# ProgrammerBoardV1_1.net
KiCad netlist of a schematic drawn in EAGLE
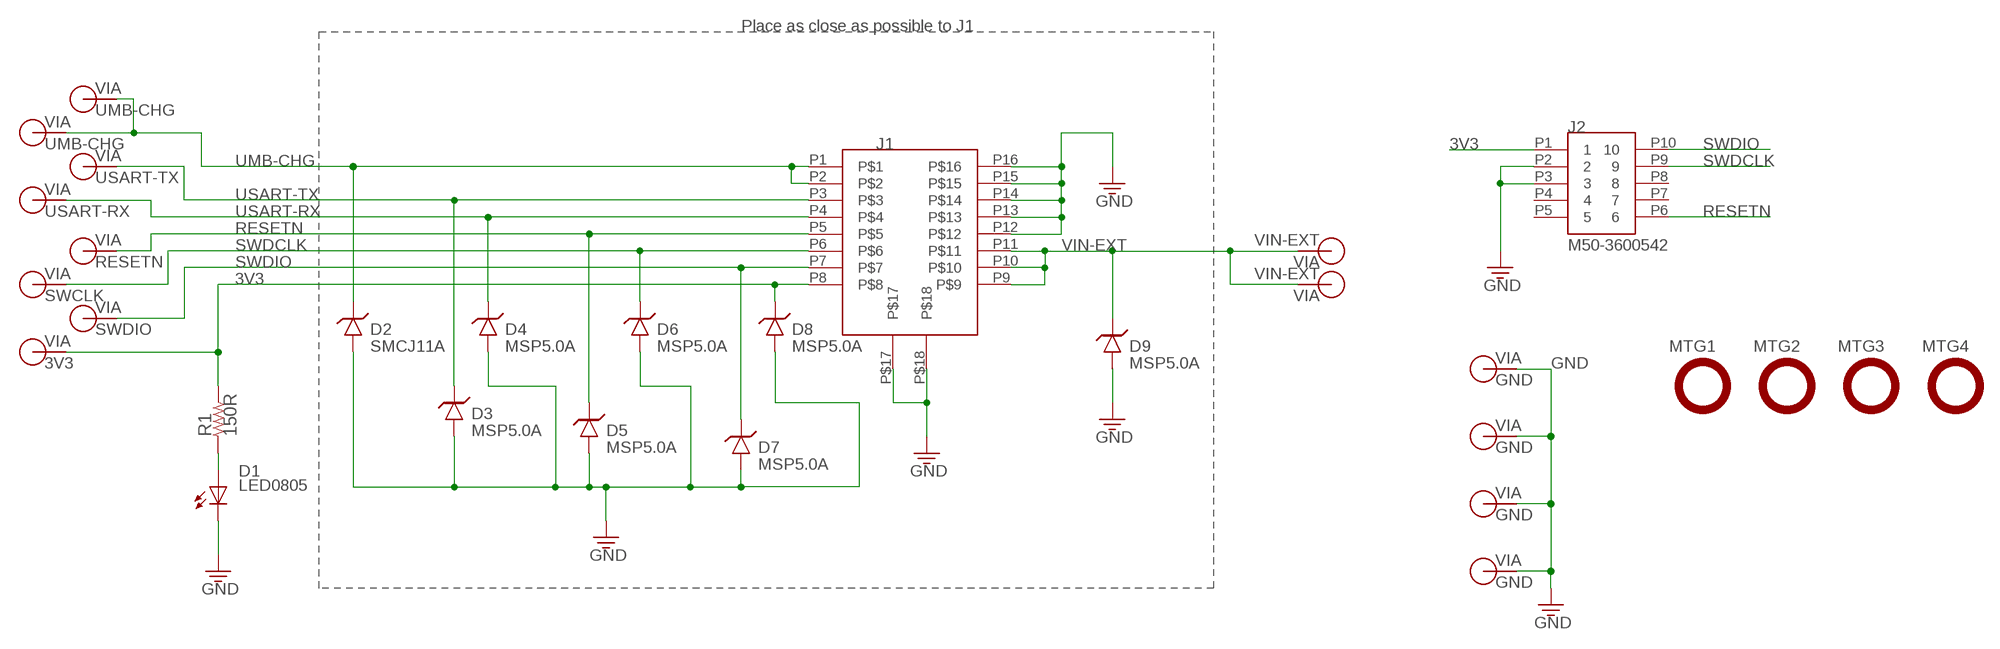
[diagram p0: schematic, sheet 1]

(export (version "E")
  (design (tool "Eeschema 10.0.6"))
  (components
    (comp (ref "D1")
      (value "LED0805")
      (footprint "eagle-import:0805-D")
      (libsource (lib "eagle-import") (part "LED0805"))
    )
    (comp (ref "D2")
      (value "SMCJ11A")
      (footprint "eagle-import:DO-214AB")
      (libsource (lib "eagle-import") (part "TVSSMCJ11A"))
    )
    (comp (ref "D3")
      (value "MSP5.0A")
      (footprint "eagle-import:MICROSMP")
      (libsource (lib "eagle-import") (part "TVSMSP"))
    )
    (comp (ref "D4")
      (value "MSP5.0A")
      (footprint "eagle-import:MICROSMP")
      (libsource (lib "eagle-import") (part "TVSMSP"))
    )
    (comp (ref "D5")
      (value "MSP5.0A")
      (footprint "eagle-import:MICROSMP")
      (libsource (lib "eagle-import") (part "TVSMSP"))
    )
    (comp (ref "D6")
      (value "MSP5.0A")
      (footprint "eagle-import:MICROSMP")
      (libsource (lib "eagle-import") (part "TVSMSP"))
    )
    (comp (ref "D7")
      (value "MSP5.0A")
      (footprint "eagle-import:MICROSMP")
      (libsource (lib "eagle-import") (part "TVSMSP"))
    )
    (comp (ref "D8")
      (value "MSP5.0A")
      (footprint "eagle-import:MICROSMP")
      (libsource (lib "eagle-import") (part "TVSMSP"))
    )
    (comp (ref "D9")
      (value "MSP5.0A")
      (footprint "eagle-import:MICROSMP")
      (libsource (lib "eagle-import") (part "TVSMSP"))
    )
    (comp (ref "J1")
      (value "FFC-16REVERSE")
      (footprint "eagle-import:68611614422-REVERSE")
      (libsource (lib "eagle-import") (part "FFC-16REVERSE"))
    )
    (comp (ref "J2")
      (value "M50-3600542")
      (footprint "eagle-import:10PINMALE")
      (libsource (lib "eagle-import") (part "10PINMALE"))
    )
    (comp (ref "MTG1")
      (value "MTG-NPTH-M2")
      (footprint "eagle-import:M2-NPTH")
      (libsource (lib "eagle-import") (part "MTG-NPTH-M2"))
    )
    (comp (ref "MTG2")
      (value "MTG-NPTH-M2")
      (footprint "eagle-import:M2-NPTH")
      (libsource (lib "eagle-import") (part "MTG-NPTH-M2"))
    )
    (comp (ref "MTG3")
      (value "MTG-NPTH-M2")
      (footprint "eagle-import:M2-NPTH")
      (libsource (lib "eagle-import") (part "MTG-NPTH-M2"))
    )
    (comp (ref "MTG4")
      (value "MTG-NPTH-M2")
      (footprint "eagle-import:M2-NPTH")
      (libsource (lib "eagle-import") (part "MTG-NPTH-M2"))
    )
    (comp (ref "R1")
      (value "150R")
      (footprint "eagle-import:0805")
      (libsource (lib "eagle-import") (part "RES0805"))
    )
    (comp (ref "V1")
      (value "GND")
      (footprint "eagle-import:VIA-60MIL")
      (libsource (lib "eagle-import") (part "VIA-60MIL"))
    )
    (comp (ref "V2")
      (value "GND")
      (footprint "eagle-import:VIA-60MIL")
      (libsource (lib "eagle-import") (part "VIA-60MIL"))
    )
    (comp (ref "V3")
      (value "GND")
      (footprint "eagle-import:VIA-60MIL")
      (libsource (lib "eagle-import") (part "VIA-60MIL"))
    )
    (comp (ref "V4")
      (value "GND")
      (footprint "eagle-import:VIA-60MIL")
      (libsource (lib "eagle-import") (part "VIA-60MIL"))
    )
    (comp (ref "V5")
      (value "SWDIO")
      (footprint "eagle-import:VIA-60MIL")
      (libsource (lib "eagle-import") (part "VIA-60MIL"))
    )
    (comp (ref "V6")
      (value "UMB-CHG")
      (footprint "eagle-import:VIA-60MIL")
      (libsource (lib "eagle-import") (part "VIA-60MIL"))
    )
    (comp (ref "V7")
      (value "UMB-CHG")
      (footprint "eagle-import:VIA-60MIL")
      (libsource (lib "eagle-import") (part "VIA-60MIL"))
    )
    (comp (ref "V8")
      (value "RESETN")
      (footprint "eagle-import:VIA-60MIL")
      (libsource (lib "eagle-import") (part "VIA-60MIL"))
    )
    (comp (ref "V9")
      (value "SWCLK")
      (footprint "eagle-import:VIA-60MIL")
      (libsource (lib "eagle-import") (part "VIA-60MIL"))
    )
    (comp (ref "V10")
      (value "3V3")
      (footprint "eagle-import:VIA-60MIL")
      (libsource (lib "eagle-import") (part "VIA-60MIL"))
    )
    (comp (ref "V11")
      (value "VIN-EXT")
      (footprint "eagle-import:VIA-60MIL")
      (libsource (lib "eagle-import") (part "VIA-60MIL"))
    )
    (comp (ref "V12")
      (value "VIN-EXT")
      (footprint "eagle-import:VIA-60MIL")
      (libsource (lib "eagle-import") (part "VIA-60MIL"))
    )
    (comp (ref "V13")
      (value "USART-RX")
      (footprint "eagle-import:VIA-60MIL")
      (libsource (lib "eagle-import") (part "VIA-60MIL"))
    )
    (comp (ref "V14")
      (value "USART-TX")
      (footprint "eagle-import:VIA-60MIL")
      (libsource (lib "eagle-import") (part "VIA-60MIL"))
    )
  )
  (nets
    (net (code "1") (name "/3V3") (class "Default")
      (node (ref "D8") (pin "C") (pinfunction "C_C") (pintype "bidirectional"))
      (node (ref "J1") (pin "P8") (pinfunction "P$8_P8") (pintype "bidirectional"))
      (node (ref "J2") (pin "P1") (pinfunction "1_P1") (pintype "bidirectional"))
      (node (ref "R1") (pin "2") (pinfunction "2_2") (pintype "passive"))
      (node (ref "V10") (pin "P$1") (pinfunction "P$1_P$1") (pintype "bidirectional"))
    )
    (net (code "2") (name "/RESETN") (class "Default")
      (node (ref "D5") (pin "C") (pinfunction "C_C") (pintype "bidirectional"))
      (node (ref "J1") (pin "P5") (pinfunction "P$5_P5") (pintype "bidirectional"))
      (node (ref "J2") (pin "P6") (pinfunction "6_P6") (pintype "bidirectional"))
      (node (ref "V8") (pin "P$1") (pinfunction "P$1_P$1") (pintype "bidirectional"))
    )
    (net (code "3") (name "/SWDCLK") (class "Default")
      (node (ref "D6") (pin "C") (pinfunction "C_C") (pintype "bidirectional"))
      (node (ref "J1") (pin "P6") (pinfunction "P$6_P6") (pintype "bidirectional"))
      (node (ref "J2") (pin "P9") (pinfunction "9_P9") (pintype "bidirectional"))
      (node (ref "V9") (pin "P$1") (pinfunction "P$1_P$1") (pintype "bidirectional"))
    )
    (net (code "4") (name "/SWDIO") (class "Default")
      (node (ref "D7") (pin "C") (pinfunction "C_C") (pintype "bidirectional"))
      (node (ref "J1") (pin "P7") (pinfunction "P$7_P7") (pintype "bidirectional"))
      (node (ref "J2") (pin "P10") (pinfunction "10_P10") (pintype "bidirectional"))
      (node (ref "V5") (pin "P$1") (pinfunction "P$1_P$1") (pintype "bidirectional"))
    )
    (net (code "5") (name "/UMB-CHG") (class "Default")
      (node (ref "D2") (pin "C") (pinfunction "C_C") (pintype "bidirectional"))
      (node (ref "J1") (pin "P1") (pinfunction "P$1_P1") (pintype "bidirectional"))
      (node (ref "J1") (pin "P2") (pinfunction "P$2_P2") (pintype "bidirectional"))
      (node (ref "V6") (pin "P$1") (pinfunction "P$1_P$1") (pintype "bidirectional"))
      (node (ref "V7") (pin "P$1") (pinfunction "P$1_P$1") (pintype "bidirectional"))
    )
    (net (code "6") (name "/USART-RX") (class "Default")
      (node (ref "D4") (pin "C") (pinfunction "C_C") (pintype "bidirectional"))
      (node (ref "J1") (pin "P4") (pinfunction "P$4_P4") (pintype "bidirectional"))
      (node (ref "V13") (pin "P$1") (pinfunction "P$1_P$1") (pintype "bidirectional"))
    )
    (net (code "7") (name "/USART-TX") (class "Default")
      (node (ref "D3") (pin "C") (pinfunction "C_C") (pintype "bidirectional"))
      (node (ref "J1") (pin "P3") (pinfunction "P$3_P3") (pintype "bidirectional"))
      (node (ref "V14") (pin "P$1") (pinfunction "P$1_P$1") (pintype "bidirectional"))
    )
    (net (code "8") (name "/VIN-EXT") (class "Default")
      (node (ref "D9") (pin "C") (pinfunction "C_C") (pintype "bidirectional"))
      (node (ref "J1") (pin "P10") (pinfunction "P$10_P10") (pintype "bidirectional"))
      (node (ref "J1") (pin "P11") (pinfunction "P$11_P11") (pintype "bidirectional"))
      (node (ref "J1") (pin "P9") (pinfunction "P$9_P9") (pintype "bidirectional"))
      (node (ref "V11") (pin "P$1") (pinfunction "P$1_P$1") (pintype "bidirectional"))
      (node (ref "V12") (pin "P$1") (pinfunction "P$1_P$1") (pintype "bidirectional"))
    )
    (net (code "9") (name "GND") (class "Default")
      (node (ref "D1") (pin "C") (pinfunction "C_C") (pintype "passive"))
      (node (ref "D2") (pin "A") (pinfunction "A_A") (pintype "bidirectional"))
      (node (ref "D3") (pin "A") (pinfunction "A_A") (pintype "bidirectional"))
      (node (ref "D4") (pin "A") (pinfunction "A_A") (pintype "bidirectional"))
      (node (ref "D5") (pin "A") (pinfunction "A_A") (pintype "bidirectional"))
      (node (ref "D6") (pin "A") (pinfunction "A_A") (pintype "bidirectional"))
      (node (ref "D7") (pin "A") (pinfunction "A_A") (pintype "bidirectional"))
      (node (ref "D8") (pin "A") (pinfunction "A_A") (pintype "bidirectional"))
      (node (ref "D9") (pin "A") (pinfunction "A_A") (pintype "bidirectional"))
      (node (ref "J1") (pin "P$17") (pinfunction "P$17_P$17") (pintype "bidirectional"))
      (node (ref "J1") (pin "P$18") (pinfunction "P$18_P$18") (pintype "bidirectional"))
      (node (ref "J1") (pin "P12") (pinfunction "P$12_P12") (pintype "bidirectional"))
      (node (ref "J1") (pin "P13") (pinfunction "P$13_P13") (pintype "bidirectional"))
      (node (ref "J1") (pin "P14") (pinfunction "P$14_P14") (pintype "bidirectional"))
      (node (ref "J1") (pin "P15") (pinfunction "P$15_P15") (pintype "bidirectional"))
      (node (ref "J1") (pin "P16") (pinfunction "P$16_P16") (pintype "bidirectional"))
      (node (ref "J2") (pin "P2") (pinfunction "2_P2") (pintype "bidirectional"))
      (node (ref "J2") (pin "P3") (pinfunction "3_P3") (pintype "bidirectional"))
      (node (ref "V1") (pin "P$1") (pinfunction "P$1_P$1") (pintype "bidirectional"))
      (node (ref "V2") (pin "P$1") (pinfunction "P$1_P$1") (pintype "bidirectional"))
      (node (ref "V3") (pin "P$1") (pinfunction "P$1_P$1") (pintype "bidirectional"))
      (node (ref "V4") (pin "P$1") (pinfunction "P$1_P$1") (pintype "bidirectional"))
    )
    (net (code "10") (name "Net-(D1-PadA)") (class "Default")
      (node (ref "D1") (pin "A") (pinfunction "A_A") (pintype "passive"))
      (node (ref "R1") (pin "1") (pinfunction "1_1") (pintype "passive"))
    )
    (net (code "11") (name "unconnected-(J2-4-PadP4)") (class "Default")
      (node (ref "J2") (pin "P4") (pinfunction "4_P4") (pintype "bidirectional"))
    )
    (net (code "12") (name "unconnected-(J2-5-PadP5)") (class "Default")
      (node (ref "J2") (pin "P5") (pinfunction "5_P5") (pintype "bidirectional"))
    )
    (net (code "13") (name "unconnected-(J2-7-PadP7)") (class "Default")
      (node (ref "J2") (pin "P7") (pinfunction "7_P7") (pintype "bidirectional"))
    )
    (net (code "14") (name "unconnected-(J2-8-PadP8)") (class "Default")
      (node (ref "J2") (pin "P8") (pinfunction "8_P8") (pintype "bidirectional"))
    )
  )
)
